# Constant_Current_Controller.net
KiCad netlist of a schematic drawn in Altium Designer
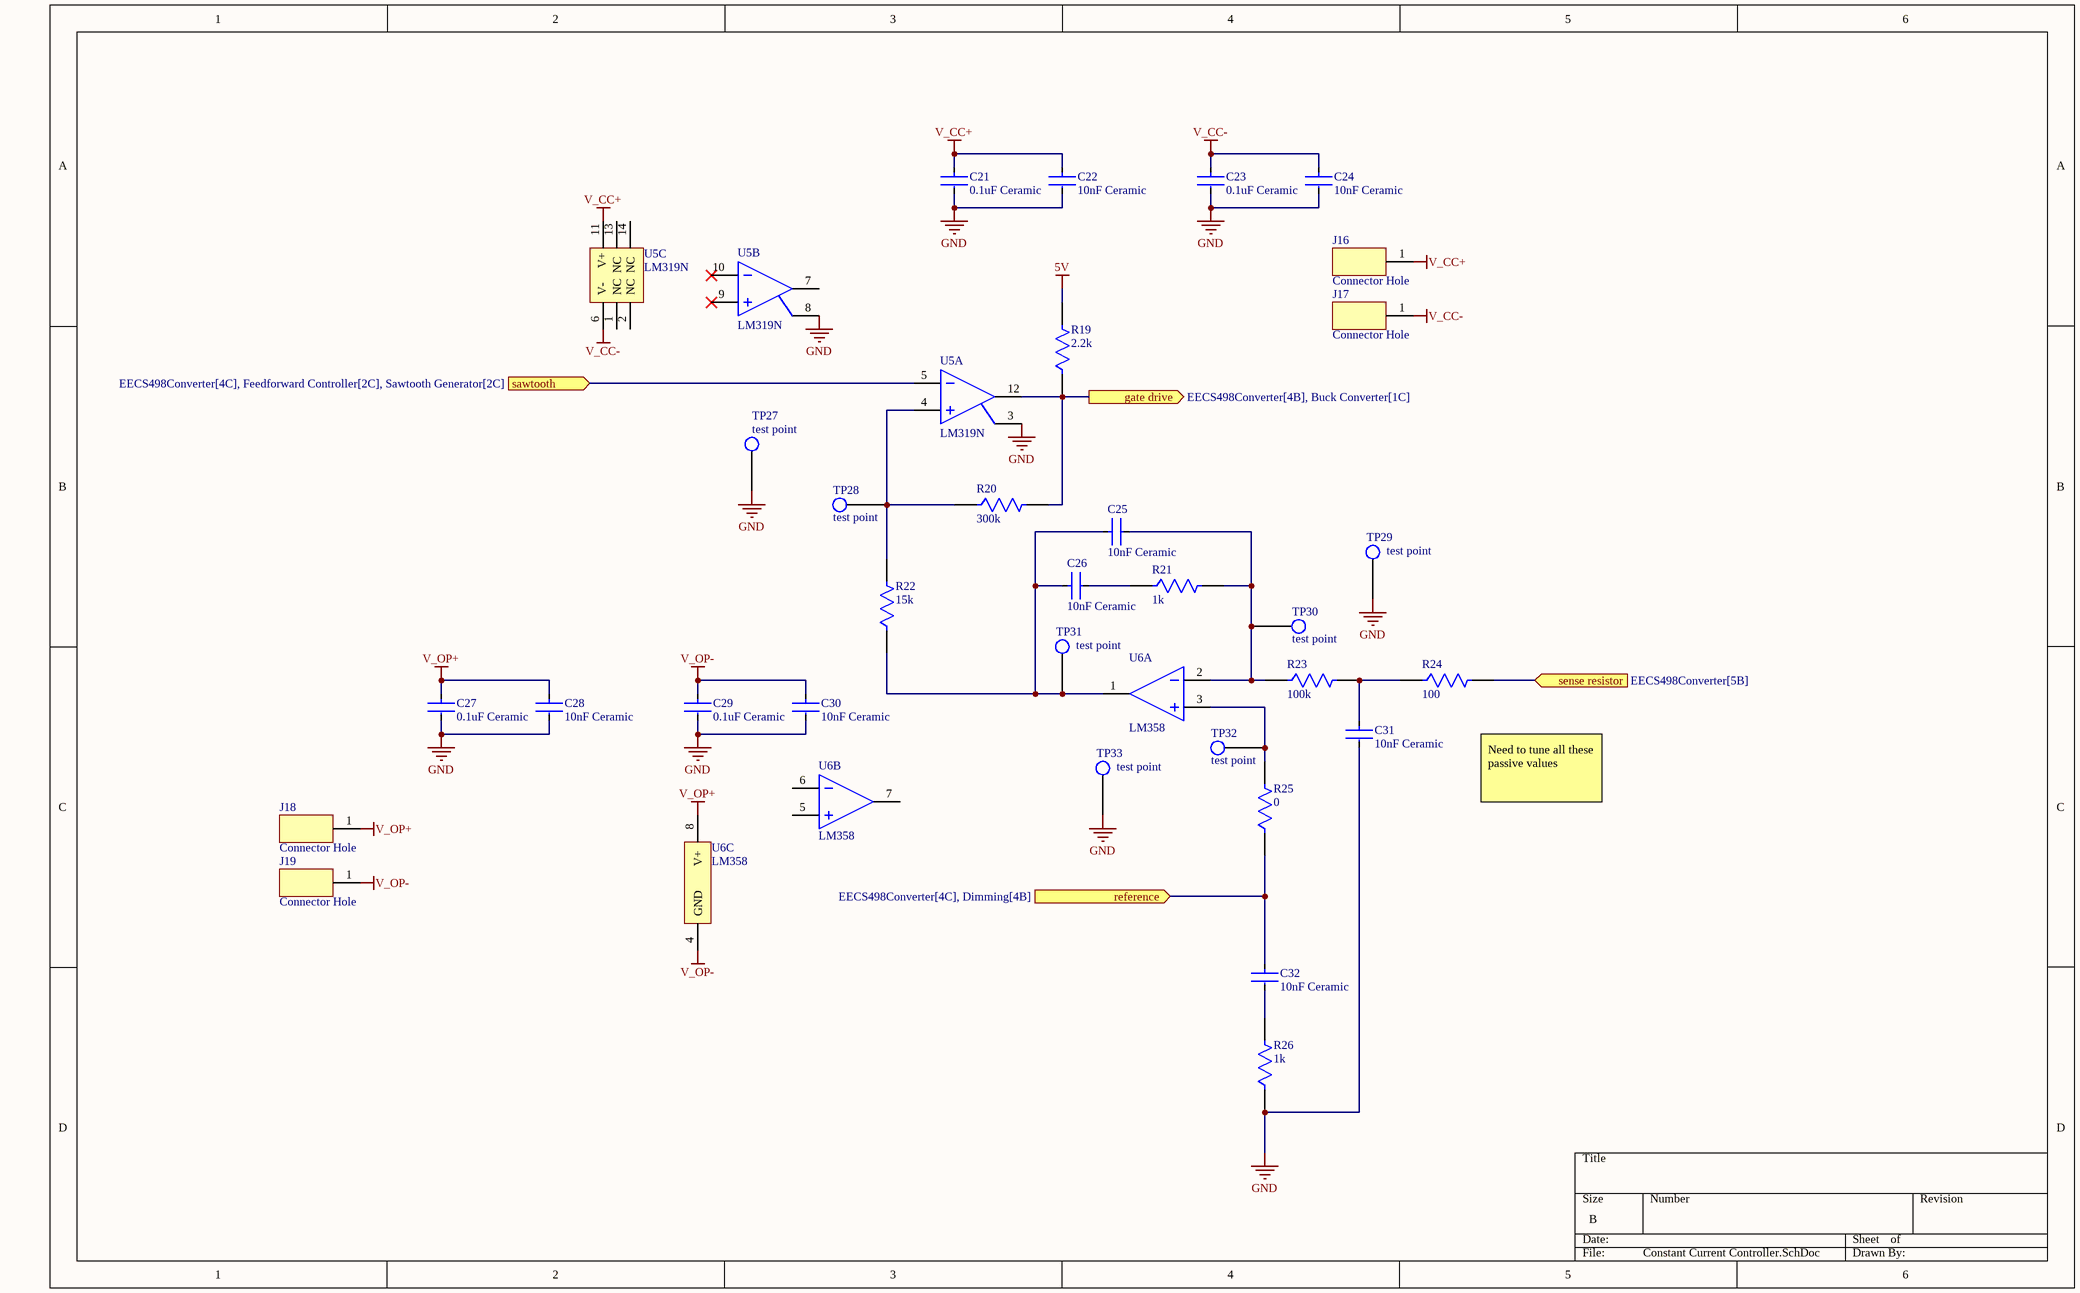
[diagram p0: Constant Current Controller.SchDoc]

(export (version "E")
  (design (tool "Eeschema 10.0.6"))
  (components
    (comp (ref "C21")
      (value "0.1uF Ceramic")
      (footprint "FP-K15H5-MFG")
      (description "CAP CER 0.1UF 50V X7R RADIAL")
      (fields (field (name "TOLERANCE") "10%") (field (name "VOLTAGE") "50V"))
      (libsource (lib "EECS498Converter") (part "0.1uF Capacitor"))
    )
    (comp (ref "C22")
      (value "10nF Ceramic")
      (footprint "FP-K15H5-MFG")
      (description "CAP CER 10nF 50V X7R RADIAL")
      (fields (field (name "TOLERANCE") "10%") (field (name "VOLTAGE") "50V"))
      (libsource (lib "EECS498Converter") (part "10nF Capacitor"))
    )
    (comp (ref "C23")
      (value "0.1uF Ceramic")
      (footprint "FP-K15H5-MFG")
      (description "CAP CER 0.1UF 50V X7R RADIAL")
      (fields (field (name "TOLERANCE") "10%") (field (name "VOLTAGE") "50V"))
      (libsource (lib "EECS498Converter") (part "0.1uF Capacitor"))
    )
    (comp (ref "C24")
      (value "10nF Ceramic")
      (footprint "FP-K15H5-MFG")
      (description "CAP CER 10nF 50V X7R RADIAL")
      (fields (field (name "TOLERANCE") "10%") (field (name "VOLTAGE") "50V"))
      (libsource (lib "EECS498Converter") (part "10nF Capacitor"))
    )
    (comp (ref "C25")
      (value "10nF Ceramic")
      (footprint "FP-K15H5-MFG")
      (description "CAP CER 10nF 50V X7R RADIAL")
      (fields (field (name "TOLERANCE") "10%") (field (name "VOLTAGE") "50V"))
      (libsource (lib "EECS498Converter") (part "10nF Capacitor"))
    )
    (comp (ref "C26")
      (value "10nF Ceramic")
      (footprint "FP-K15H5-MFG")
      (description "CAP CER 10nF 50V X7R RADIAL")
      (fields (field (name "TOLERANCE") "10%") (field (name "VOLTAGE") "50V"))
      (libsource (lib "EECS498Converter") (part "10nF Capacitor"))
    )
    (comp (ref "C27")
      (value "0.1uF Ceramic")
      (footprint "FP-K15H5-MFG")
      (description "CAP CER 0.1UF 50V X7R RADIAL")
      (fields (field (name "TOLERANCE") "10%") (field (name "VOLTAGE") "50V"))
      (libsource (lib "EECS498Converter") (part "0.1uF Capacitor"))
    )
    (comp (ref "C28")
      (value "10nF Ceramic")
      (footprint "FP-K15H5-MFG")
      (description "CAP CER 10nF 50V X7R RADIAL")
      (fields (field (name "TOLERANCE") "10%") (field (name "VOLTAGE") "50V"))
      (libsource (lib "EECS498Converter") (part "10nF Capacitor"))
    )
    (comp (ref "C29")
      (value "0.1uF Ceramic")
      (footprint "FP-K15H5-MFG")
      (description "CAP CER 0.1UF 50V X7R RADIAL")
      (fields (field (name "TOLERANCE") "10%") (field (name "VOLTAGE") "50V"))
      (libsource (lib "EECS498Converter") (part "0.1uF Capacitor"))
    )
    (comp (ref "C30")
      (value "10nF Ceramic")
      (footprint "FP-K15H5-MFG")
      (description "CAP CER 10nF 50V X7R RADIAL")
      (fields (field (name "TOLERANCE") "10%") (field (name "VOLTAGE") "50V"))
      (libsource (lib "EECS498Converter") (part "10nF Capacitor"))
    )
    (comp (ref "C31")
      (value "10nF Ceramic")
      (footprint "FP-K15H5-MFG")
      (description "CAP CER 10nF 50V X7R RADIAL")
      (fields (field (name "TOLERANCE") "10%") (field (name "VOLTAGE") "50V"))
      (libsource (lib "EECS498Converter") (part "10nF Capacitor"))
    )
    (comp (ref "C32")
      (value "10nF Ceramic")
      (footprint "FP-K15H5-MFG")
      (description "CAP CER 10nF 50V X7R RADIAL")
      (fields (field (name "TOLERANCE") "10%") (field (name "VOLTAGE") "50V"))
      (libsource (lib "EECS498Converter") (part "10nF Capacitor"))
    )
    (comp (ref "J16")
      (value "Connector Hole")
      (footprint "Connector Hole")
      (libsource (lib "EECS498Converter") (part "Connector Hole"))
    )
    (comp (ref "J17")
      (value "Connector Hole")
      (footprint "Connector Hole")
      (libsource (lib "EECS498Converter") (part "Connector Hole"))
    )
    (comp (ref "J18")
      (value "Connector Hole")
      (footprint "Connector Hole")
      (libsource (lib "EECS498Converter") (part "Connector Hole"))
    )
    (comp (ref "J19")
      (value "Connector Hole")
      (footprint "Connector Hole")
      (libsource (lib "EECS498Converter") (part "Connector Hole"))
    )
    (comp (ref "R19")
      (value "2.2k")
      (footprint "FP-RLR07-MFG")
      (description "Resistor, ± 1%, 250 mW, Axial Leaded, Metal Film, Military Reliability")
      (fields (field (name "TOLERANCE") "1%"))
      (libsource (lib "EECS498Converter") (part "Resistor"))
    )
    (comp (ref "R20")
      (value "300k")
      (footprint "FP-RLR07-MFG")
      (description "Resistor, ± 1%, 250 mW, Axial Leaded, Metal Film, Military Reliability")
      (fields (field (name "TOLERANCE") "1%"))
      (libsource (lib "EECS498Converter") (part "Resistor"))
    )
    (comp (ref "R21")
      (value "1k")
      (footprint "FP-RLR07-MFG")
      (description "Resistor, ± 1%, 250 mW, Axial Leaded, Metal Film, Military Reliability")
      (fields (field (name "TOLERANCE") "1%"))
      (libsource (lib "EECS498Converter") (part "Resistor"))
    )
    (comp (ref "R22")
      (value "15k")
      (footprint "FP-RLR07-MFG")
      (description "Resistor, ± 1%, 250 mW, Axial Leaded, Metal Film, Military Reliability")
      (fields (field (name "TOLERANCE") "1%"))
      (libsource (lib "EECS498Converter") (part "Resistor"))
    )
    (comp (ref "R23")
      (value "100k")
      (footprint "FP-RLR07-MFG")
      (description "Resistor, ± 1%, 250 mW, Axial Leaded, Metal Film, Military Reliability")
      (fields (field (name "TOLERANCE") "1%"))
      (libsource (lib "EECS498Converter") (part "Resistor"))
    )
    (comp (ref "R24")
      (value "100")
      (footprint "FP-RLR07-MFG")
      (description "Resistor, ± 1%, 250 mW, Axial Leaded, Metal Film, Military Reliability")
      (fields (field (name "TOLERANCE") "1%"))
      (libsource (lib "EECS498Converter") (part "Resistor"))
    )
    (comp (ref "R25")
      (value "0")
      (footprint "FP-RLR07-MFG")
      (description "Resistor, ± 1%, 250 mW, Axial Leaded, Metal Film, Military Reliability")
      (fields (field (name "TOLERANCE") "1%"))
      (libsource (lib "EECS498Converter") (part "Resistor"))
    )
    (comp (ref "R26")
      (value "1k")
      (footprint "FP-RLR07-MFG")
      (description "Resistor, ± 1%, 250 mW, Axial Leaded, Metal Film, Military Reliability")
      (fields (field (name "TOLERANCE") "1%"))
      (libsource (lib "EECS498Converter") (part "Resistor"))
    )
    (comp (ref "TP27")
      (value "test point")
      (footprint "test point")
      (libsource (lib "EECS498Converter") (part "test point"))
    )
    (comp (ref "TP28")
      (value "test point")
      (footprint "test point")
      (libsource (lib "EECS498Converter") (part "test point"))
    )
    (comp (ref "TP29")
      (value "test point")
      (footprint "test point")
      (libsource (lib "EECS498Converter") (part "test point"))
    )
    (comp (ref "TP30")
      (value "test point")
      (footprint "test point")
      (libsource (lib "EECS498Converter") (part "test point"))
    )
    (comp (ref "TP31")
      (value "test point")
      (footprint "test point")
      (libsource (lib "EECS498Converter") (part "test point"))
    )
    (comp (ref "TP32")
      (value "test point")
      (footprint "test point")
      (libsource (lib "EECS498Converter") (part "test point"))
    )
    (comp (ref "TP33")
      (value "test point")
      (footprint "test point")
      (libsource (lib "EECS498Converter") (part "test point"))
    )
    (comp (ref "U5")
      (value "LM319N")
      (footprint "LM319_DIP14")
      (description "High Speed Dual Comparator, 14-pin MDIP")
      (fields (field (name "MANUFACTURER") "Texas Instruments"))
      (libsource (lib "EECS498Converter") (part "LM319N"))
    )
    (comp (ref "U6")
      (value "LM358")
      (footprint "DIP8")
      (description "Low Power Dual Operational Amplifier, 8-pin MDIP, Pb-Free")
      (fields (field (name "MANUFACTURER") "Texas Instruments"))
      (libsource (lib "") (part "LM358_1"))
    )
  )
  (nets
    (net (code "1") (name "/gate drive") (class "Default")
      (node (ref "R19") (pin "1") (pinfunction "1_1") (pintype "passive"))
      (node (ref "R20") (pin "2") (pinfunction "2_2") (pintype "passive"))
      (node (ref "U5") (pin "12") (pinfunction "OUT1_12") (pintype "passive"))
    )
    (net (code "2") (name "/reference") (class "Default")
      (node (ref "C32") (pin "1") (pinfunction "1_1") (pintype "passive"))
      (node (ref "R25") (pin "1") (pinfunction "1_1") (pintype "passive"))
    )
    (net (code "3") (name "/sawtooth") (class "Default")
      (node (ref "U5") (pin "5") (pinfunction "IN1-_5") (pintype "passive"))
    )
    (net (code "4") (name "/sense resistor") (class "Default")
      (node (ref "R24") (pin "2") (pinfunction "2_2") (pintype "passive"))
    )
    (net (code "5") (name "5V") (class "Default")
      (node (ref "R19") (pin "2") (pinfunction "2_2") (pintype "passive"))
    )
    (net (code "6") (name "GND") (class "Default")
      (node (ref "C21") (pin "2") (pinfunction "2_2") (pintype "passive"))
      (node (ref "C22") (pin "2") (pinfunction "2_2") (pintype "passive"))
      (node (ref "C23") (pin "2") (pinfunction "2_2") (pintype "passive"))
      (node (ref "C24") (pin "2") (pinfunction "2_2") (pintype "passive"))
      (node (ref "C27") (pin "2") (pinfunction "2_2") (pintype "passive"))
      (node (ref "C28") (pin "2") (pinfunction "2_2") (pintype "passive"))
      (node (ref "C29") (pin "2") (pinfunction "2_2") (pintype "passive"))
      (node (ref "C30") (pin "2") (pinfunction "2_2") (pintype "passive"))
      (node (ref "C31") (pin "2") (pinfunction "2_2") (pintype "passive"))
      (node (ref "R26") (pin "1") (pinfunction "1_1") (pintype "passive"))
      (node (ref "TP27") (pin "1") (pintype "passive"))
      (node (ref "TP29") (pin "1") (pintype "passive"))
      (node (ref "TP33") (pin "1") (pintype "passive"))
      (node (ref "U5") (pin "3") (pinfunction "GND1_3") (pintype "passive"))
      (node (ref "U5") (pin "8") (pinfunction "GND2_8") (pintype "passive"))
    )
    (net (code "7") (name "Net-(C26-Pad2)") (class "Default")
      (node (ref "C26") (pin "2") (pinfunction "2_2") (pintype "passive"))
      (node (ref "R21") (pin "1") (pinfunction "1_1") (pintype "passive"))
    )
    (net (code "8") (name "Net-(C31-Pad1)") (class "Default")
      (node (ref "C31") (pin "1") (pinfunction "1_1") (pintype "passive"))
      (node (ref "R23") (pin "2") (pinfunction "2_2") (pintype "passive"))
      (node (ref "R24") (pin "1") (pinfunction "1_1") (pintype "passive"))
    )
    (net (code "9") (name "Net-(C32-Pad2)") (class "Default")
      (node (ref "C32") (pin "2") (pinfunction "2_2") (pintype "passive"))
      (node (ref "R26") (pin "2") (pinfunction "2_2") (pintype "passive"))
    )
    (net (code "10") (name "Net-(U5A-IN1+)") (class "Default")
      (node (ref "R20") (pin "1") (pinfunction "1_1") (pintype "passive"))
      (node (ref "R22") (pin "2") (pinfunction "2_2") (pintype "passive"))
      (node (ref "TP28") (pin "1") (pintype "passive"))
      (node (ref "U5") (pin "4") (pinfunction "IN1+_4") (pintype "passive"))
    )
    (net (code "11") (name "Net-(U6A-INA+)") (class "Default")
      (node (ref "R25") (pin "2") (pinfunction "2_2") (pintype "passive"))
      (node (ref "TP32") (pin "1") (pintype "passive"))
      (node (ref "U6") (pin "3") (pinfunction "INA+_3") (pintype "passive"))
    )
    (net (code "12") (name "Net-(U6A-INA-)") (class "Default")
      (node (ref "C25") (pin "2") (pinfunction "2_2") (pintype "passive"))
      (node (ref "R21") (pin "2") (pinfunction "2_2") (pintype "passive"))
      (node (ref "R23") (pin "1") (pinfunction "1_1") (pintype "passive"))
      (node (ref "TP30") (pin "1") (pintype "passive"))
      (node (ref "U6") (pin "2") (pinfunction "INA-_2") (pintype "passive"))
    )
    (net (code "13") (name "Net-(U6A-OUTA)") (class "Default")
      (node (ref "C25") (pin "1") (pinfunction "1_1") (pintype "passive"))
      (node (ref "C26") (pin "1") (pinfunction "1_1") (pintype "passive"))
      (node (ref "R22") (pin "1") (pinfunction "1_1") (pintype "passive"))
      (node (ref "TP31") (pin "1") (pintype "passive"))
      (node (ref "U6") (pin "1") (pinfunction "OUTA_1") (pintype "passive"))
    )
    (net (code "14") (name "V_CC+") (class "Default")
      (node (ref "C21") (pin "1") (pinfunction "1_1") (pintype "passive"))
      (node (ref "C22") (pin "1") (pinfunction "1_1") (pintype "passive"))
      (node (ref "J16") (pin "1") (pinfunction "1_1") (pintype "passive"))
      (node (ref "U5") (pin "11") (pinfunction "V+_11") (pintype "passive"))
    )
    (net (code "15") (name "V_CC-") (class "Default")
      (node (ref "C23") (pin "1") (pinfunction "1_1") (pintype "passive"))
      (node (ref "C24") (pin "1") (pinfunction "1_1") (pintype "passive"))
      (node (ref "J17") (pin "1") (pinfunction "1_1") (pintype "passive"))
      (node (ref "U5") (pin "6") (pinfunction "V-_6") (pintype "passive"))
    )
    (net (code "16") (name "V_OP+") (class "Default")
      (node (ref "C27") (pin "1") (pinfunction "1_1") (pintype "passive"))
      (node (ref "C28") (pin "1") (pinfunction "1_1") (pintype "passive"))
      (node (ref "J18") (pin "1") (pinfunction "1_1") (pintype "passive"))
      (node (ref "U6") (pin "8") (pinfunction "V+_8") (pintype "passive"))
    )
    (net (code "17") (name "V_OP-") (class "Default")
      (node (ref "C29") (pin "1") (pinfunction "1_1") (pintype "passive"))
      (node (ref "C30") (pin "1") (pinfunction "1_1") (pintype "passive"))
      (node (ref "J19") (pin "1") (pinfunction "1_1") (pintype "passive"))
      (node (ref "U6") (pin "4") (pinfunction "GND_4") (pintype "power_in"))
    )
    (net (code "18") (name "unconnected-(U5B-IN2+-Pad9)") (class "Default")
      (node (ref "U5") (pin "9") (pinfunction "IN2+_9") (pintype "passive+no_connect"))
    )
    (net (code "19") (name "unconnected-(U5B-IN2--Pad10)") (class "Default")
      (node (ref "U5") (pin "10") (pinfunction "IN2-_10") (pintype "passive+no_connect"))
    )
    (net (code "20") (name "unconnected-(U5B-OUT2-Pad7)") (class "Default")
      (node (ref "U5") (pin "7") (pinfunction "OUT2_7") (pintype "passive"))
    )
    (net (code "21") (name "unconnected-(U5C-NC-Pad1)") (class "Default")
      (node (ref "U5") (pin "1") (pinfunction "NC_1") (pintype "passive"))
    )
    (net (code "22") (name "unconnected-(U5C-NC-Pad2)") (class "Default")
      (node (ref "U5") (pin "2") (pinfunction "NC_2") (pintype "passive"))
    )
    (net (code "23") (name "unconnected-(U5C-NC-Pad13)") (class "Default")
      (node (ref "U5") (pin "13") (pinfunction "NC_13") (pintype "passive"))
    )
    (net (code "24") (name "unconnected-(U5C-NC-Pad14)") (class "Default")
      (node (ref "U5") (pin "14") (pinfunction "NC_14") (pintype "passive"))
    )
    (net (code "25") (name "unconnected-(U6B-INB+-Pad5)") (class "Default")
      (node (ref "U6") (pin "5") (pinfunction "INB+_5") (pintype "passive"))
    )
    (net (code "26") (name "unconnected-(U6B-INB--Pad6)") (class "Default")
      (node (ref "U6") (pin "6") (pinfunction "INB-_6") (pintype "passive"))
    )
    (net (code "27") (name "unconnected-(U6B-OUTB-Pad7)") (class "Default")
      (node (ref "U6") (pin "7") (pinfunction "OUTB_7") (pintype "passive"))
    )
  )
)
